# Battery_Manager.net
KiCad netlist of a schematic drawn in Altium Designer
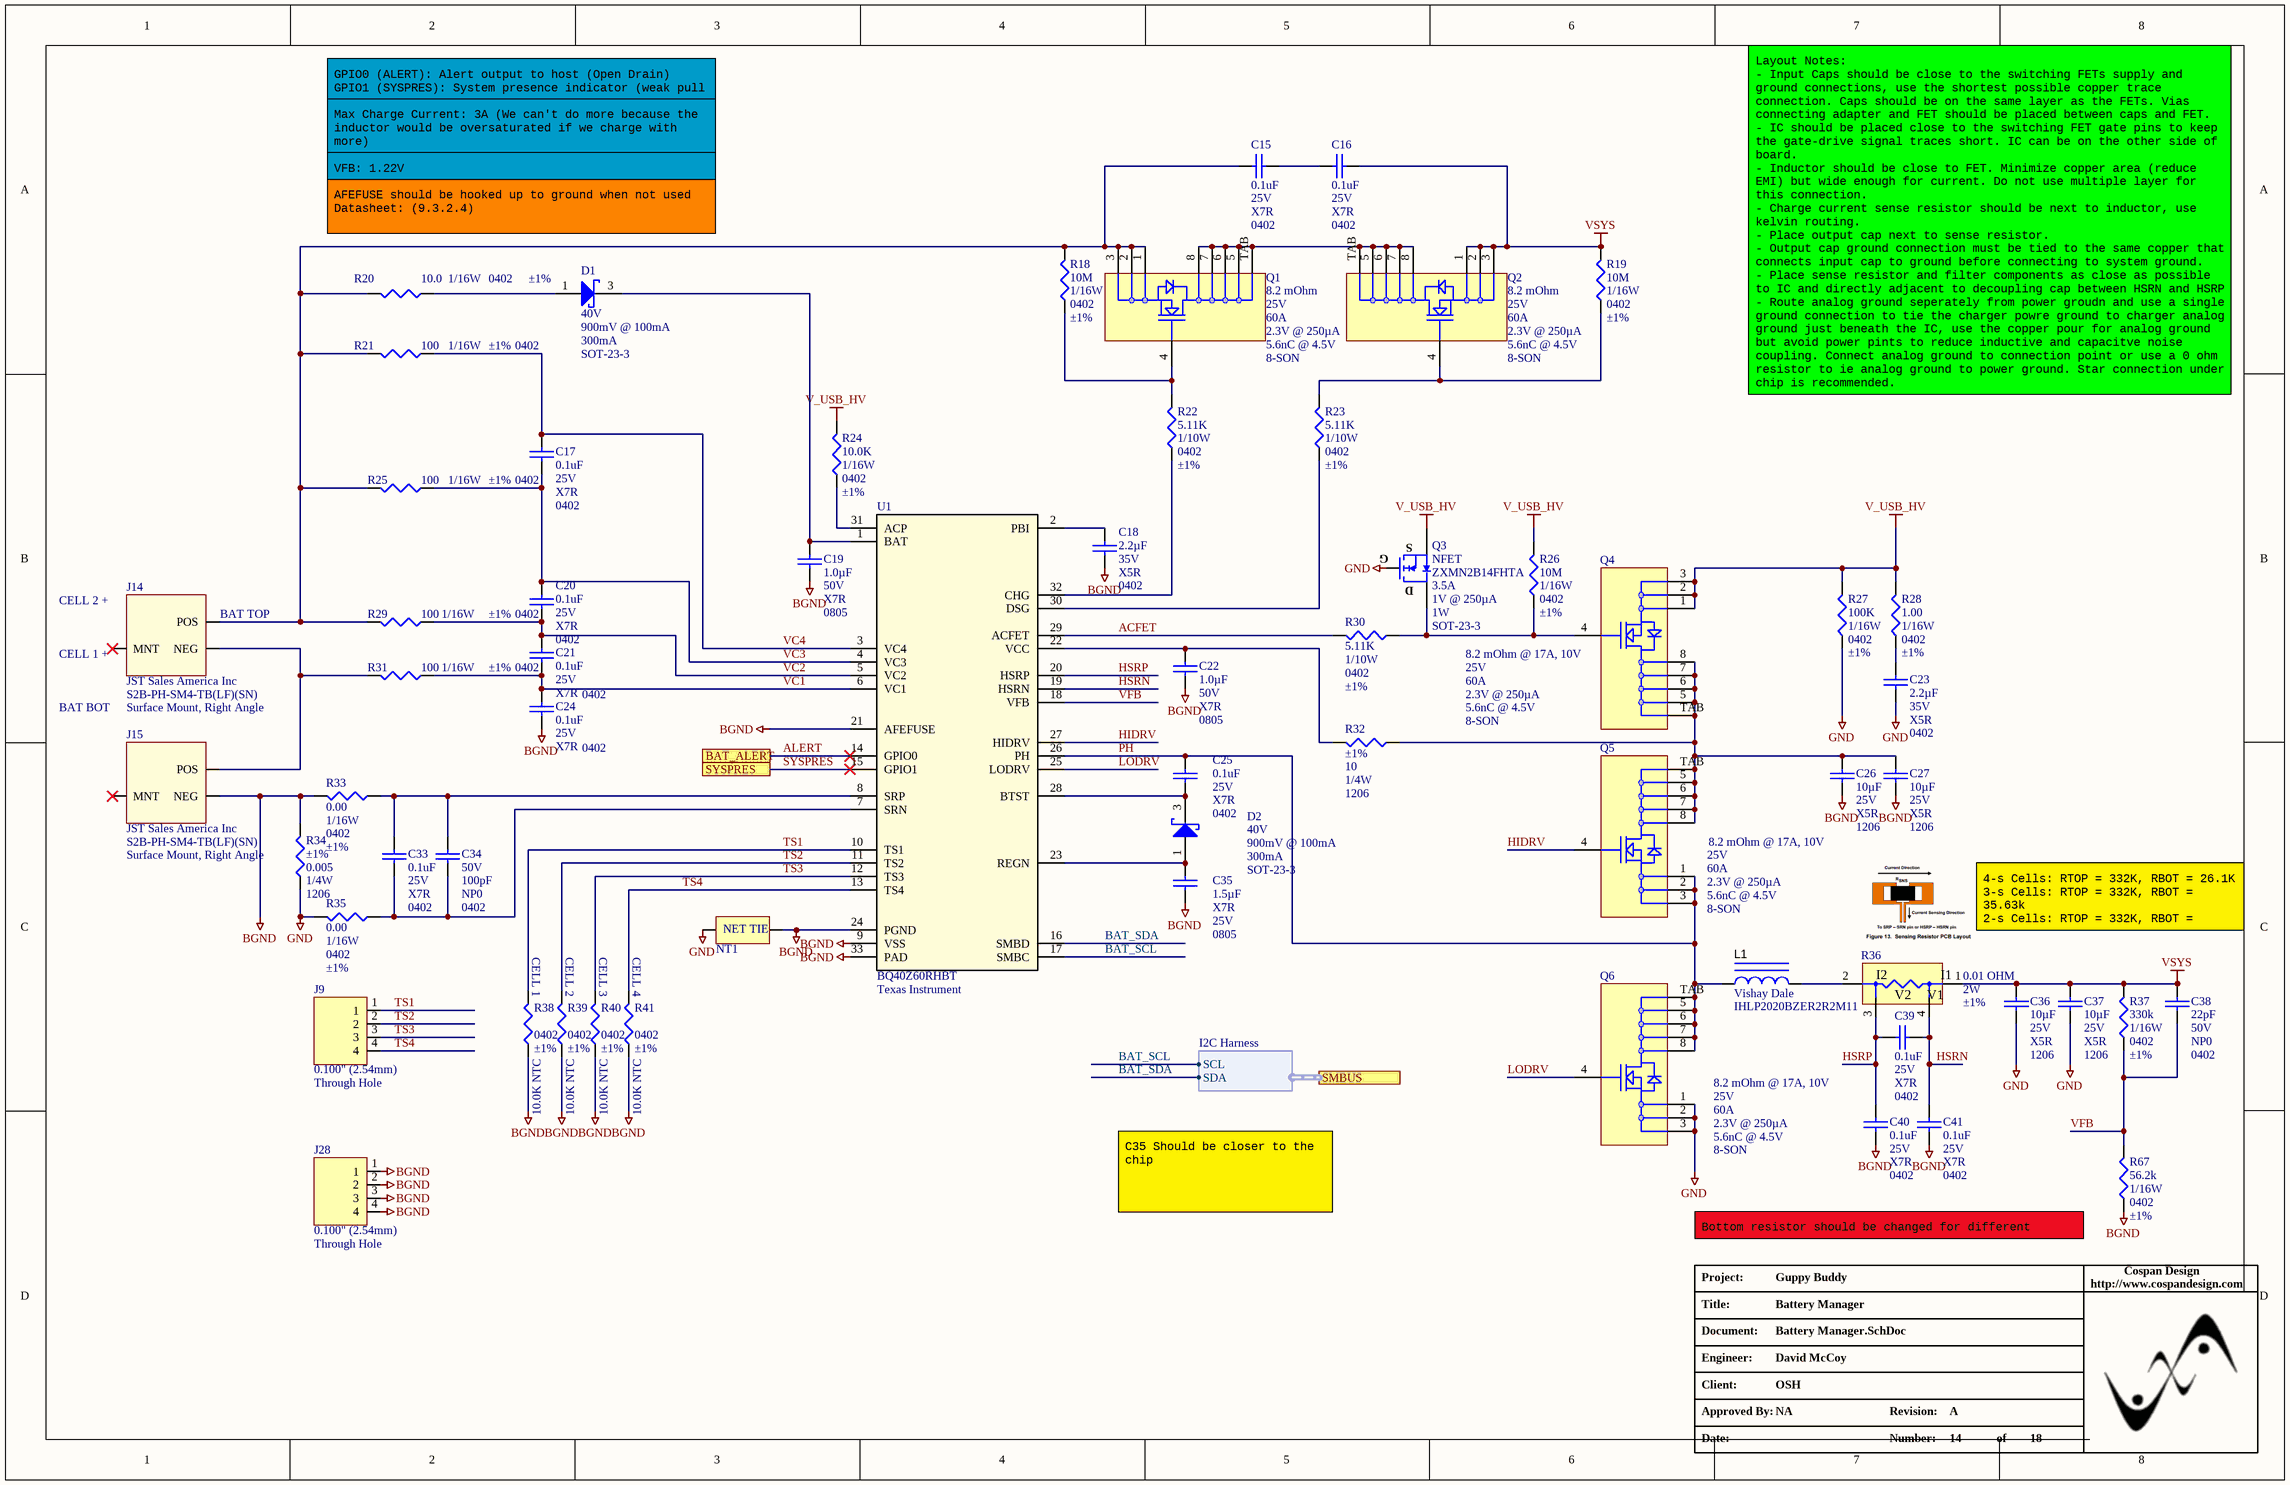
[diagram p0: Battery Manager.SchDoc]

(export (version "E")
  (design (tool "Eeschema 10.0.6"))
  (components
    (comp (ref "C15")
      (value "C_0402_0.1UF_25V")
      (footprint "C_0402")
      (description "CAP CER 0.1UF 25V X6S 0402")
      (fields
        (field (name "TOLERANCE") "10%")
        (field (name "CAPACITANCE") "0.1uF")
        (field (name "VOLTAGE - RATED") "25V")
        (field (name "TEMPERATURE COEFFICIENT") "X7R")
        (field (name "PACKAGE / CASE") "0402")
      )
      (libsource (lib "Cospan Design") (part "C_0402_0.1UF_25V"))
    )
    (comp (ref "C16")
      (value "C_0402_0.1UF_25V")
      (footprint "C_0402")
      (description "CAP CER 0.1UF 25V X6S 0402")
      (fields
        (field (name "TOLERANCE") "10%")
        (field (name "CAPACITANCE") "0.1uF")
        (field (name "VOLTAGE - RATED") "25V")
        (field (name "TEMPERATURE COEFFICIENT") "X7R")
        (field (name "PACKAGE / CASE") "0402")
      )
      (libsource (lib "Cospan Design") (part "C_0402_0.1UF_25V"))
    )
    (comp (ref "C17")
      (value "C_0402_0.1UF_25V")
      (footprint "C_0402")
      (description "CAP CER 0.1UF 25V X6S 0402")
      (fields
        (field (name "TOLERANCE") "10%")
        (field (name "CAPACITANCE") "0.1uF")
        (field (name "VOLTAGE - RATED") "25V")
        (field (name "TEMPERATURE COEFFICIENT") "X7R")
        (field (name "PACKAGE / CASE") "0402")
      )
      (libsource (lib "Cospan Design") (part "C_0402_0.1UF_25V"))
    )
    (comp (ref "C18")
      (value "C_0402_2.2uF_35V")
      (footprint "C_ERA-0402")
      (description "CAP CER 2.2UF 35V 20% X5R 0402")
      (fields
        (field (name "MANUFACTURER") "TDK Corporation")
        (field (name "MANUFACTURER PART NUMBER") "C1005X5R1V225K050BC")
        (field (name "CAPACITANCE") "2.2µF")
        (field (name "VOLTAGE - RATED") "35V")
        (field (name "TEMPERATURE COEFFICIENT") "X5R")
        (field (name "PACKAGE / CASE") "0402")
      )
      (libsource (lib "Main LibraryX") (part "C_0402_2.2uF_35V"))
    )
    (comp (ref "C19")
      (value "1.0uF")
      (footprint "C_ERA-0805")
      (description "CAP CER 1UF 50V X7R 0805")
      (fields
        (field (name "TOLERANCE") "10%")
        (field (name "CAPACITANCE") "1.0µF")
        (field (name "VOLTAGE - RATED") "50V")
        (field (name "TEMPERATURE COEFFICIENT") "X7R")
        (field (name "PACKAGE / CASE") "0805")
        (field (name "VOLTAGE") "50V")
      )
      (libsource (lib "Main LibraryX") (part "C_0805_1.0uF_50V"))
    )
    (comp (ref "C20")
      (value "C_0402_0.1UF_25V")
      (footprint "C_0402")
      (description "CAP CER 0.1UF 25V X6S 0402")
      (fields
        (field (name "TOLERANCE") "10%")
        (field (name "CAPACITANCE") "0.1uF")
        (field (name "VOLTAGE - RATED") "25V")
        (field (name "TEMPERATURE COEFFICIENT") "X7R")
        (field (name "PACKAGE / CASE") "0402")
      )
      (libsource (lib "Cospan Design") (part "C_0402_0.1UF_25V"))
    )
    (comp (ref "C21")
      (value "C_0402_0.1UF_25V")
      (footprint "C_0402")
      (description "CAP CER 0.1UF 25V X6S 0402")
      (fields
        (field (name "TOLERANCE") "10%")
        (field (name "CAPACITANCE") "0.1uF")
        (field (name "VOLTAGE - RATED") "25V")
        (field (name "TEMPERATURE COEFFICIENT") "X7R")
        (field (name "PACKAGE / CASE") "0402")
      )
      (libsource (lib "Cospan Design") (part "C_0402_0.1UF_25V"))
    )
    (comp (ref "C22")
      (value "1.0uF")
      (footprint "C_ERA-0805")
      (description "CAP CER 1UF 50V X7R 0805")
      (fields
        (field (name "TOLERANCE") "10%")
        (field (name "CAPACITANCE") "1.0µF")
        (field (name "VOLTAGE - RATED") "50V")
        (field (name "TEMPERATURE COEFFICIENT") "X7R")
        (field (name "PACKAGE / CASE") "0805")
        (field (name "VOLTAGE") "50V")
      )
      (libsource (lib "Main LibraryX") (part "C_0805_1.0uF_50V"))
    )
    (comp (ref "C23")
      (value "C_0402_2.2uF_35V")
      (footprint "C_ERA-0402")
      (description "CAP CER 2.2UF 35V 20% X5R 0402")
      (fields
        (field (name "MANUFACTURER") "TDK Corporation")
        (field (name "MANUFACTURER PART NUMBER") "C1005X5R1V225K050BC")
        (field (name "CAPACITANCE") "2.2µF")
        (field (name "VOLTAGE - RATED") "35V")
        (field (name "TEMPERATURE COEFFICIENT") "X5R")
        (field (name "PACKAGE / CASE") "0402")
      )
      (libsource (lib "Main LibraryX") (part "C_0402_2.2uF_35V"))
    )
    (comp (ref "C24")
      (value "C_0402_0.1UF_25V")
      (footprint "C_0402")
      (description "CAP CER 0.1UF 25V X6S 0402")
      (fields
        (field (name "TOLERANCE") "10%")
        (field (name "CAPACITANCE") "0.1uF")
        (field (name "VOLTAGE - RATED") "25V")
        (field (name "TEMPERATURE COEFFICIENT") "X7R")
        (field (name "PACKAGE / CASE") "0402")
      )
      (libsource (lib "Cospan Design") (part "C_0402_0.1UF_25V"))
    )
    (comp (ref "C25")
      (value "C_0402_0.1UF_25V")
      (footprint "C_0402")
      (description "CAP CER 0.1UF 25V X6S 0402")
      (fields
        (field (name "TOLERANCE") "10%")
        (field (name "CAPACITANCE") "0.1uF")
        (field (name "VOLTAGE - RATED") "25V")
        (field (name "TEMPERATURE COEFFICIENT") "X7R")
        (field (name "PACKAGE / CASE") "0402")
      )
      (libsource (lib "Cospan Design") (part "C_0402_0.1UF_25V"))
    )
    (comp (ref "C26")
      (value "10µF")
      (footprint "CAP-1206")
      (description "CAP CER 10UF 25V X5R 1206")
      (fields
        (field (name "TOLERANCE") "10%")
        (field (name "CAPACITANCE") "10µF")
        (field (name "VOLTAGE - RATED") "25V")
        (field (name "TEMPERATURE COEFFICIENT") "X5R")
        (field (name "PACKAGE / CASE") "1206")
        (field (name "VOLTAGE") "25V")
      )
      (libsource (lib "Main LibraryX") (part "C_1206_10UF_25V"))
    )
    (comp (ref "C27")
      (value "10µF")
      (footprint "CAP-1206")
      (description "CAP CER 10UF 25V X5R 1206")
      (fields
        (field (name "TOLERANCE") "10%")
        (field (name "CAPACITANCE") "10µF")
        (field (name "VOLTAGE - RATED") "25V")
        (field (name "TEMPERATURE COEFFICIENT") "X5R")
        (field (name "PACKAGE / CASE") "1206")
        (field (name "VOLTAGE") "25V")
      )
      (libsource (lib "Main LibraryX") (part "C_1206_10UF_25V"))
    )
    (comp (ref "C33")
      (value "C_0402_0.1UF_25V")
      (footprint "C_0402")
      (description "CAP CER 0.1UF 25V X6S 0402")
      (fields
        (field (name "TOLERANCE") "10%")
        (field (name "CAPACITANCE") "0.1uF")
        (field (name "VOLTAGE - RATED") "25V")
        (field (name "TEMPERATURE COEFFICIENT") "X7R")
        (field (name "PACKAGE / CASE") "0402")
      )
      (libsource (lib "Cospan Design") (part "C_0402_0.1UF_25V"))
    )
    (comp (ref "C34")
      (value "100pF")
      (footprint "C_0402")
      (description "CAP CER 100PF 50V 5% C0G 0402")
      (fields
        (field (name "MANUFACTURER") "Murata Electronics North America")
        (field (name "MANUFACTURER PART NUMBER") "GRM1555C1H101JA01D")
        (field (name "VOLTAGE - RATED") "50V")
        (field (name "CAPACITANCE") "100pF")
        (field (name "TEMPERATURE COEFFICIENT") "NP0")
        (field (name "PACKAGE / CASE") "0402")
      )
      (libsource (lib "Main LibraryX") (part "C_0402_100PF"))
    )
    (comp (ref "C35")
      (value "C_0805_1.5uF_25V")
      (footprint "C_ERA-0805")
      (description "1.5µF ±10% 25V Ceramic Capacitor X7R 0805 (2012 Metric)")
      (fields
        (field (name "MANUFACTURER") "Murata Electronics North America")
        (field (name "MANUFACTURER PART NUMBER") "GRM21BR71E155KA88L")
        (field (name "CAPACITANCE") "1.5µF")
        (field (name "VOLTAGE - RATED") "X7R")
        (field (name "TEMPERATURE COEFFICIENT") "25V")
        (field (name "PACKAGE / CASE") "0805")
      )
      (libsource (lib "Cospan Design") (part "C_0805_1.5uF_25V"))
    )
    (comp (ref "C36")
      (value "10µF")
      (footprint "CAP-1206")
      (description "CAP CER 10UF 25V X5R 1206")
      (fields
        (field (name "TOLERANCE") "10%")
        (field (name "CAPACITANCE") "10µF")
        (field (name "VOLTAGE - RATED") "25V")
        (field (name "TEMPERATURE COEFFICIENT") "X5R")
        (field (name "PACKAGE / CASE") "1206")
        (field (name "VOLTAGE") "25V")
      )
      (libsource (lib "Main LibraryX") (part "C_1206_10UF_25V"))
    )
    (comp (ref "C37")
      (value "10µF")
      (footprint "CAP-1206")
      (description "CAP CER 10UF 25V X5R 1206")
      (fields
        (field (name "TOLERANCE") "10%")
        (field (name "CAPACITANCE") "10µF")
        (field (name "VOLTAGE - RATED") "25V")
        (field (name "TEMPERATURE COEFFICIENT") "X5R")
        (field (name "PACKAGE / CASE") "1206")
        (field (name "VOLTAGE") "25V")
      )
      (libsource (lib "Main LibraryX") (part "C_1206_10UF_25V"))
    )
    (comp (ref "C38")
      (value "22pF")
      (footprint "C_ERA-0402")
      (description "CAP CER 22PF 50V NP0 0402")
      (fields
        (field (name "MANUFACTURER") "Murata Electronics North America")
        (field (name "MANUFACTURER PART NUMBER") "GRM1555C1H220FA01D")
        (field (name "CAPACITANCE") "22pF")
        (field (name "VOLTAGE - RATED") "50V")
        (field (name "TEMPERATURE COEFFICIENT") "NP0")
        (field (name "PACKAGE / CASE") "0402")
      )
      (libsource (lib "Main LibraryX") (part "C_0402_22PF_50V"))
    )
    (comp (ref "C39")
      (value "C_0402_0.1UF_25V")
      (footprint "C_0402")
      (description "CAP CER 0.1UF 25V X6S 0402")
      (fields
        (field (name "TOLERANCE") "10%")
        (field (name "CAPACITANCE") "0.1uF")
        (field (name "VOLTAGE - RATED") "25V")
        (field (name "TEMPERATURE COEFFICIENT") "X7R")
        (field (name "PACKAGE / CASE") "0402")
      )
      (libsource (lib "Cospan Design") (part "C_0402_0.1UF_25V"))
    )
    (comp (ref "C40")
      (value "C_0402_0.1UF_25V")
      (footprint "C_0402")
      (description "CAP CER 0.1UF 25V X6S 0402")
      (fields
        (field (name "TOLERANCE") "10%")
        (field (name "CAPACITANCE") "0.1uF")
        (field (name "VOLTAGE - RATED") "25V")
        (field (name "TEMPERATURE COEFFICIENT") "X7R")
        (field (name "PACKAGE / CASE") "0402")
      )
      (libsource (lib "Cospan Design") (part "C_0402_0.1UF_25V"))
    )
    (comp (ref "C41")
      (value "C_0402_0.1UF_25V")
      (footprint "C_0402")
      (description "CAP CER 0.1UF 25V X6S 0402")
      (fields
        (field (name "TOLERANCE") "10%")
        (field (name "CAPACITANCE") "0.1uF")
        (field (name "VOLTAGE - RATED") "25V")
        (field (name "TEMPERATURE COEFFICIENT") "X7R")
        (field (name "PACKAGE / CASE") "0402")
      )
      (libsource (lib "Cospan Design") (part "C_0402_0.1UF_25V"))
    )
    (comp (ref "D1")
      (value "BAT54")
      (footprint "SOT23")
      (description "DIODE SCHOTTKY 40V 300MA SOT-23")
      (fields
        (field (name "VOLTAGE - DC REVERSE (VR) (MAX)") "40V")
        (field (name "VOLTAGE - FORWARD (VF) (MAX) @ IF") "900mV @ 100mA")
        (field (name "CURRENT - AVERAGE RECTIFIED (IO)") "300mA")
        (field (name "PACKAGE / CASE") "SOT-23-3")
      )
      (libsource (lib "Main Library") (part "D_SCHOTT_BAT54WFILM"))
    )
    (comp (ref "D2")
      (value "BAT54")
      (footprint "SOT23")
      (description "DIODE SCHOTTKY 40V 300MA SOT-23")
      (fields
        (field (name "VOLTAGE - DC REVERSE (VR) (MAX)") "40V")
        (field (name "VOLTAGE - FORWARD (VF) (MAX) @ IF") "900mV @ 100mA")
        (field (name "CURRENT - AVERAGE RECTIFIED (IO)") "300mA")
        (field (name "PACKAGE / CASE") "SOT-23-3")
      )
      (libsource (lib "Main Library") (part "D_SCHOTT_BAT54WFILM"))
    )
    (comp (ref "J9")
      (value "J_HDR1X4_THRHOLE_VERT")
      (footprint "HDR_1X4")
      (description "CONN HEADER .100\" 4POS TIN PCB")
      (fields
        (field (name "MANUFACTURER") "Samtec")
        (field (name "MANUFACTURER PART NUMBER") "TSW-104-07-T-S")
        (field (name "PITCH") "0.100\" (2.54mm)")
        (field (name "MOUNTING TYPE") "Through Hole")
      )
      (libsource (lib "Main Library") (part "J_HDR1X4_THRHOLE_VERT"))
    )
    (comp (ref "J14")
      (value "J_LIPO_BAT_CONNECTOR")
      (footprint "HDR_1X2_LIPO_BATTERY")
      (description "CONN HEADER PH SIDE 2POS 2MM SMD")
      (fields
        (field (name "MANUFACTURER") "JST Sales America Inc")
        (field (name "MANUFACTURER PART NUMBER") "S2B-PH-SM4-TB(LF)(SN)")
        (field (name "MOUNTING TYPE") "Surface Mount, Right Angle")
      )
      (libsource (lib "Main Library") (part "J_LIPO_BAT_CONNECTOR"))
    )
    (comp (ref "J15")
      (value "J_LIPO_BAT_CONNECTOR")
      (footprint "HDR_1X2_LIPO_BATTERY")
      (description "CONN HEADER PH SIDE 2POS 2MM SMD")
      (fields
        (field (name "MANUFACTURER") "JST Sales America Inc")
        (field (name "MANUFACTURER PART NUMBER") "S2B-PH-SM4-TB(LF)(SN)")
        (field (name "MOUNTING TYPE") "Surface Mount, Right Angle")
      )
      (libsource (lib "Main Library") (part "J_LIPO_BAT_CONNECTOR"))
    )
    (comp (ref "J28")
      (value "J_HDR1X4_THRHOLE_VERT")
      (footprint "HDR_1X4")
      (description "CONN HEADER .100\" 4POS TIN PCB")
      (fields
        (field (name "MANUFACTURER") "Samtec")
        (field (name "MANUFACTURER PART NUMBER") "TSW-104-07-T-S")
        (field (name "PITCH") "0.100\" (2.54mm)")
        (field (name "MOUNTING TYPE") "Through Hole")
      )
      (libsource (lib "Main Library") (part "J_HDR1X4_THRHOLE_VERT"))
    )
    (comp (ref "L1")
      (value "L_IHLP2020BZER2R2M11")
      (footprint "IHLP-2020BZ")
      (description "2.2µH Shielded Molded Inductor 5A 37.7 mOhm Max")
      (fields
        (field (name "TOLERANCE") "±20%")
        (field (name "MANUFACTURER") "Vishay Dale")
        (field (name "MANUFACTURER PART NUMBER") "IHLP2020BZER2R2M11")
      )
      (libsource (lib "Cospan Design") (part "L_IHLP2020BZER2R2M11"))
    )
    (comp (ref "NT1")
      (value "NET_TIE")
      (footprint "NET_TIE")
      (libsource (lib "Cospan Design") (part "NET_TIE"))
    )
    (comp (ref "Q1")
      (value "N-Channel Nex_FET")
      (footprint "Q_TDSON-8 NexFET")
      (description "MOSFET N-CH 25V 60A 8-SON")
      (fields
        (field (name "MANUFACTURER") "Texas Instruments")
        (field (name "MANUFACTURER PART NUMBER") "CSD16409Q3")
        (field (name "RDS ON (MAX) @ ID, VGS") "8.2 mOhm")
        (field (name "DRAIN TO SOURCE VOLTAGE (VDSS)") "25V")
        (field (name "CURRENT - CONTINUOUS DRAIN (ID) @ 25° C") "60A")
        (field (name "VGS(TH) (MAX) @ ID") "2.3V @ 250µA")
        (field (name "GATE CHARGE (QG) @ VGS") "5.6nC @ 4.5V")
        (field (name "PACKAGE / CASE") "8-SON")
      )
      (libsource (lib "Main Library") (part "Q_N-CH_8SON_60A_9.5mOHM"))
    )
    (comp (ref "Q2")
      (value "N-Channel Nex_FET")
      (footprint "Q_TDSON-8 NexFET")
      (description "MOSFET N-CH 25V 60A 8-SON")
      (fields
        (field (name "MANUFACTURER") "Texas Instruments")
        (field (name "MANUFACTURER PART NUMBER") "CSD16409Q3")
        (field (name "RDS ON (MAX) @ ID, VGS") "8.2 mOhm")
        (field (name "DRAIN TO SOURCE VOLTAGE (VDSS)") "25V")
        (field (name "CURRENT - CONTINUOUS DRAIN (ID) @ 25° C") "60A")
        (field (name "VGS(TH) (MAX) @ ID") "2.3V @ 250µA")
        (field (name "GATE CHARGE (QG) @ VGS") "5.6nC @ 4.5V")
        (field (name "PACKAGE / CASE") "8-SON")
      )
      (libsource (lib "Main Library") (part "Q_N-CH_8SON_60A_9.5mOHM"))
    )
    (comp (ref "Q3")
      (value "NFET")
      (footprint "SOT-23A")
      (description "MOSFET N-CH 20V 3.5A SOT23-3")
      (fields
        (field (name "MANUFACTURER") "Diodes/Zetex")
        (field (name "MANUFACTURER PART NUMBER") "ZXMN2B14FHTA")
        (field (name "CURRENT - CONTINUOUS DRAIN (ID) @ 25° C") "3.5A")
        (field (name "VGS(TH) (MAX) @ ID") "1V @ 250µA")
        (field (name "POWER - MAX") "1W")
        (field (name "PACKAGE / CASE") "SOT-23-3")
      )
      (libsource (lib "Main LibraryX") (part "Q_NFET_3.50A_SOT23"))
    )
    (comp (ref "Q4")
      (value "N-Channel Nex_FET")
      (footprint "Q_TDSON-8 NexFET")
      (description "MOSFET N-CH 25V 60A 8-SON")
      (fields
        (field (name "MANUFACTURER") "Texas Instruments")
        (field (name "MANUFACTURER PART NUMBER") "CSD16409Q3")
        (field (name "RDS ON (MAX) @ ID, VGS") "8.2 mOhm @ 17A, 10V")
        (field (name "DRAIN TO SOURCE VOLTAGE (VDSS)") "25V")
        (field (name "CURRENT - CONTINUOUS DRAIN (ID) @ 25° C") "60A")
        (field (name "VGS(TH) (MAX) @ ID") "2.3V @ 250µA")
        (field (name "GATE CHARGE (QG) @ VGS") "5.6nC @ 4.5V")
        (field (name "PACKAGE / CASE") "8-SON")
      )
      (libsource (lib "Main Library") (part "Q_N-CH_8SON_60A_9.5mOHM"))
    )
    (comp (ref "Q5")
      (value "N-Channel Nex_FET")
      (footprint "Q_TDSON-8 NexFET")
      (description "MOSFET N-CH 25V 60A 8-SON")
      (fields
        (field (name "MANUFACTURER") "Texas Instruments")
        (field (name "MANUFACTURER PART NUMBER") "CSD16409Q3")
        (field (name "RDS ON (MAX) @ ID, VGS") "8.2 mOhm @ 17A, 10V")
        (field (name "DRAIN TO SOURCE VOLTAGE (VDSS)") "25V")
        (field (name "CURRENT - CONTINUOUS DRAIN (ID) @ 25° C") "60A")
        (field (name "VGS(TH) (MAX) @ ID") "2.3V @ 250µA")
        (field (name "GATE CHARGE (QG) @ VGS") "5.6nC @ 4.5V")
        (field (name "PACKAGE / CASE") "8-SON")
      )
      (libsource (lib "Main Library") (part "Q_N-CH_8SON_60A_9.5mOHM"))
    )
    (comp (ref "Q6")
      (value "N-Channel Nex_FET")
      (footprint "Q_TDSON-8 NexFET")
      (description "MOSFET N-CH 25V 60A 8-SON")
      (fields
        (field (name "MANUFACTURER") "Texas Instruments")
        (field (name "MANUFACTURER PART NUMBER") "CSD16409Q3")
        (field (name "RDS ON (MAX) @ ID, VGS") "8.2 mOhm @ 17A, 10V")
        (field (name "DRAIN TO SOURCE VOLTAGE (VDSS)") "25V")
        (field (name "CURRENT - CONTINUOUS DRAIN (ID) @ 25° C") "60A")
        (field (name "VGS(TH) (MAX) @ ID") "2.3V @ 250µA")
        (field (name "GATE CHARGE (QG) @ VGS") "5.6nC @ 4.5V")
        (field (name "PACKAGE / CASE") "8-SON")
      )
      (libsource (lib "Main Library") (part "Q_N-CH_8SON_60A_9.5mOHM"))
    )
    (comp (ref "R18")
      (value "R_0402_10M")
      (footprint "R_0402")
      (description "RES SMD 10M OHM 1% 1/16W 0402")
      (fields
        (field (name "MANUFACTURER") "Yageo")
        (field (name "MANUFACTURER PART NUMBER") "RC0402FR-0710ML")
        (field (name "RESISTANCE IN OHMS") "10M")
        (field (name "POWER (WATTS)") "1/16W")
        (field (name "CASE") "0402")
        (field (name "TOLERANCE") "±1%")
      )
      (libsource (lib "Cospan Design") (part "R_0402_10M"))
    )
    (comp (ref "R19")
      (value "R_0402_10M")
      (footprint "R_0402")
      (description "RES SMD 10M OHM 1% 1/16W 0402")
      (fields
        (field (name "MANUFACTURER") "Yageo")
        (field (name "MANUFACTURER PART NUMBER") "RC0402FR-0710ML")
        (field (name "RESISTANCE IN OHMS") "10M")
        (field (name "POWER (WATTS)") "1/16W")
        (field (name "CASE") "0402")
        (field (name "TOLERANCE") "±1%")
      )
      (libsource (lib "Cospan Design") (part "R_0402_10M"))
    )
    (comp (ref "R20")
      (value "R_0402_10.0")
      (footprint "R_0402")
      (description "RES 10.0 OHM 1/16W 1% 0402 SMD")
      (fields
        (field (name "MANUFACTURER") "Yageo")
        (field (name "MANUFACTURER PART NUMBER") "RC0402FR-0710RL")
        (field (name "RESISTANCE IN OHMS") "10.0")
        (field (name "POWER (WATTS)") "1/16W")
        (field (name "CASE") "0402")
        (field (name "TOLERANCE") "±1%")
      )
      (libsource (lib "Main LibraryX") (part "R_0402_10.0"))
    )
    (comp (ref "R21")
      (value "R_0402_100.0")
      (footprint "R_0402")
      (description "RES 100 OHM 1/16W 1% 0402 SMD")
      (fields
        (field (name "MANUFACTURER") "Yageo")
        (field (name "MANUFACTURER PART NUMBER") "RC0402FR-07100RL")
        (field (name "CASE") "0402")
        (field (name "RESISTANCE IN OHMS") "100")
        (field (name "POWER (WATTS)") "1/16W")
        (field (name "TOLERANCE") "±1%")
      )
      (libsource (lib "Main LibraryX") (part "R_0402_100.0"))
    )
    (comp (ref "R22")
      (value "5.11k Ohms")
      (footprint "R_0402")
      (description "RES 5.11K OHM 1/10W 1% 0402 SMD")
      (fields
        (field (name "MANUFACTURER") "Panasonic - ECG")
        (field (name "MANUFACTURER PART NUMBER") "ERJ-2RKF5111X")
        (field (name "RESISTANCE IN OHMS") "5.11K")
        (field (name "POWER (WATTS)") "1/10W")
        (field (name "CASE") "0402")
        (field (name "TOLERANCE") "±1%")
      )
      (libsource (lib "Main Library") (part "R_0402_5.11K"))
    )
    (comp (ref "R23")
      (value "5.11k Ohms")
      (footprint "R_0402")
      (description "RES 5.11K OHM 1/10W 1% 0402 SMD")
      (fields
        (field (name "MANUFACTURER") "Panasonic - ECG")
        (field (name "MANUFACTURER PART NUMBER") "ERJ-2RKF5111X")
        (field (name "RESISTANCE IN OHMS") "5.11K")
        (field (name "POWER (WATTS)") "1/10W")
        (field (name "CASE") "0402")
        (field (name "TOLERANCE") "±1%")
      )
      (libsource (lib "Main Library") (part "R_0402_5.11K"))
    )
    (comp (ref "R24")
      (value "R_0402_10.0K")
      (footprint "R_0402")
      (description "RES 10.0K OHM 1/16W 1% 0402 SMD")
      (fields
        (field (name "MANUFACTURER") "Stackpole Electronics Inc")
        (field (name "MANUFACTURER PART NUMBER") "RMCF0402FT10K0")
        (field (name "RESISTANCE IN OHMS") "10.0K")
        (field (name "POWER (WATTS)") "1/16W")
        (field (name "CASE") "0402")
        (field (name "TOLERANCE") "±1%")
      )
      (libsource (lib "Main Library") (part "R_0402_10.0K"))
    )
    (comp (ref "R25")
      (value "R_0402_100.0")
      (footprint "R_0402")
      (description "RES 100 OHM 1/16W 1% 0402 SMD")
      (fields
        (field (name "MANUFACTURER") "Yageo")
        (field (name "MANUFACTURER PART NUMBER") "RC0402FR-07100RL")
        (field (name "CASE") "0402")
        (field (name "RESISTANCE IN OHMS") "100")
        (field (name "POWER (WATTS)") "1/16W")
        (field (name "TOLERANCE") "±1%")
      )
      (libsource (lib "Main LibraryX") (part "R_0402_100.0"))
    )
    (comp (ref "R26")
      (value "R_0402_10M")
      (footprint "R_0402")
      (description "RES SMD 10M OHM 1% 1/16W 0402")
      (fields
        (field (name "MANUFACTURER") "Yageo")
        (field (name "MANUFACTURER PART NUMBER") "RC0402FR-0710ML")
        (field (name "RESISTANCE IN OHMS") "10M")
        (field (name "POWER (WATTS)") "1/16W")
        (field (name "CASE") "0402")
        (field (name "TOLERANCE") "±1%")
      )
      (libsource (lib "Cospan Design") (part "R_0402_10M"))
    )
    (comp (ref "R27")
      (value "R_0402_100.0K")
      (footprint "R_0402")
      (description "RES 100K OHM 1/16W 1% 0402 SMD")
      (fields
        (field (name "MANUFACTURER") "Stackpole Electronics Inc")
        (field (name "MANUFACTURER PART NUMBER") "RMCF0402FT100K")
        (field (name "RESISTANCE IN OHMS") "100K")
        (field (name "POWER (WATTS)") "1/16W")
        (field (name "CASE") "0402")
        (field (name "TOLERANCE") "±1%")
      )
      (libsource (lib "Main Library") (part "R_0402_100.0K"))
    )
    (comp (ref "R28")
      (value "1.0 Ohms")
      (footprint "R_0402")
      (description "RES 1.00 OHM 1/16W 1% 0402 SMD")
      (fields
        (field (name "MANUFACTURER") "Yageo")
        (field (name "MANUFACTURER PART NUMBER") "RC0402FR-071RL")
        (field (name "RESISTANCE IN OHMS") "1.00")
        (field (name "POWER (WATTS)") "1/16W")
        (field (name "CASE") "0402")
        (field (name "TOLERANCE") "±1%")
      )
      (libsource (lib "Main Library") (part "R_0402_1.00"))
    )
    (comp (ref "R29")
      (value "R_0402_100.0")
      (footprint "R_0402")
      (description "RES 100 OHM 1/16W 1% 0402 SMD")
      (fields
        (field (name "MANUFACTURER") "Yageo")
        (field (name "MANUFACTURER PART NUMBER") "RC0402FR-07100RL")
        (field (name "CASE") "0402")
        (field (name "RESISTANCE IN OHMS") "100")
        (field (name "POWER (WATTS)") "1/16W")
        (field (name "TOLERANCE") "±1%")
      )
      (libsource (lib "Main LibraryX") (part "R_0402_100.0"))
    )
    (comp (ref "R30")
      (value "5.11k Ohms")
      (footprint "R_0402")
      (description "RES 5.11K OHM 1/10W 1% 0402 SMD")
      (fields
        (field (name "MANUFACTURER") "Panasonic - ECG")
        (field (name "MANUFACTURER PART NUMBER") "ERJ-2RKF5111X")
        (field (name "RESISTANCE IN OHMS") "5.11K")
        (field (name "POWER (WATTS)") "1/10W")
        (field (name "CASE") "0402")
        (field (name "TOLERANCE") "±1%")
      )
      (libsource (lib "Main Library") (part "R_0402_5.11K"))
    )
    (comp (ref "R31")
      (value "R_0402_100.0")
      (footprint "R_0402")
      (description "RES 100 OHM 1/16W 1% 0402 SMD")
      (fields
        (field (name "MANUFACTURER") "Yageo")
        (field (name "MANUFACTURER PART NUMBER") "RC0402FR-07100RL")
        (field (name "CASE") "0402")
        (field (name "RESISTANCE IN OHMS") "100")
        (field (name "POWER (WATTS)") "1/16W")
        (field (name "TOLERANCE") "±1%")
      )
      (libsource (lib "Main LibraryX") (part "R_0402_100.0"))
    )
    (comp (ref "R32")
      (value "R_1206_10")
      (footprint "R_1206")
      (description "RES SMD 10 OHM 1% 1/4W 1206")
      (fields
        (field (name "MANUFACTURER") "Yageo")
        (field (name "MANUFACTURER PART NUMBER") "RC1206FR-0710RL")
        (field (name "TOLERANCE") "±1%")
        (field (name "RESISTANCE IN OHMS") "10")
        (field (name "POWER (WATTS)") "1/4W")
        (field (name "CASE") "1206")
      )
      (libsource (lib "Cospan Design") (part "R_1206_10"))
    )
    (comp (ref "R33")
      (value "0.0 Ohms")
      (footprint "R_0402")
      (description "RES 0.00 OHM 1/16W 1% 0402 SMD")
      (fields
        (field (name "MANUFACTURER") "Yageo")
        (field (name "MANUFACTURER PART NUMBER") "RC0402JR-070RL")
        (field (name "RESISTANCE IN OHMS") "0.00")
        (field (name "POWER (WATTS)") "1/16W")
        (field (name "CASE") "0402")
        (field (name "TOLERANCE") "±1%")
      )
      (libsource (lib "Cospan Design") (part "R_0402_0.00"))
    )
    (comp (ref "R34")
      (value "R_1206_0.005")
      (footprint "R_1206")
      (description "RES SMD 0.005 OHM 1% 1W 1206")
      (fields
        (field (name "MANUFACTURER") "Stackpole Electronics Inc.")
        (field (name "MANUFACTURER PART NUMBER") "CSRF1206FT5L00")
        (field (name "TOLERANCE") "±1%")
        (field (name "RESISTANCE IN OHMS") "0.005")
        (field (name "POWER (WATTS)") "1/4W")
        (field (name "CASE") "1206")
      )
      (libsource (lib "Cospan Design") (part "R_1206_0.005"))
    )
    (comp (ref "R35")
      (value "0.0 Ohms")
      (footprint "R_0402")
      (description "RES 0.00 OHM 1/16W 1% 0402 SMD")
      (fields
        (field (name "MANUFACTURER") "Yageo")
        (field (name "MANUFACTURER PART NUMBER") "RC0402JR-070RL")
        (field (name "RESISTANCE IN OHMS") "0.00")
        (field (name "POWER (WATTS)") "1/16W")
        (field (name "CASE") "0402")
        (field (name "TOLERANCE") "±1%")
      )
      (libsource (lib "Cospan Design") (part "R_0402_0.00"))
    )
    (comp (ref "R36")
      (value "0.01 OHM")
      (footprint "R_LVK25_0.003")
      (description "RES SMD 0.01 OHM 1% 2W 1224")
      (fields
        (field (name "MANUFACTURER") "Ohmite")
        (field (name "MANUFACTURER PART NUMBER") "LVK25R010FER")
        (field (name "POWER (WATTS)") "2W")
        (field (name "TOLERANCE") "±1%")
      )
      (libsource (lib "Main Library") (part "R_0.010SENSE_LK20"))
    )
    (comp (ref "R37")
      (value "R_0402_330K")
      (footprint "R_0402")
      (description "RES SMD 330K OHM 1% 1/16W 0402")
      (fields
        (field (name "MANUFACTURER") "Yageo")
        (field (name "MANUFACTURER PART NUMBER") "RC0402FR-07330KL")
        (field (name "RESISTANCE IN OHMS") "330k")
        (field (name "POWER (WATTS)") "1/16W")
        (field (name "CASE") "0402")
        (field (name "TOLERANCE") "±1%")
      )
      (libsource (lib "Cospan Design") (part "R_0402_330K"))
    )
    (comp (ref "R38")
      (value "R_0402_NTC_10.0K")
      (footprint "R_0402")
      (description "NTC Thermistor 10k 0402 (1005 Metric)")
      (fields
        (field (name "MANUFACTURER") "Murata Electronics North America")
        (field (name "MANUFACTURER PART NUMBER") "NCP15XH103F03RC")
        (field (name "RESISTANCE IN OHMS") "10.0K NTC")
        (field (name "CASE") "0402")
        (field (name "TOLERANCE") "±1%")
      )
      (libsource (lib "Cospan Design") (part "R_0402_NTC_10.0K"))
    )
    (comp (ref "R39")
      (value "R_0402_NTC_10.0K")
      (footprint "R_0402")
      (description "NTC Thermistor 10k 0402 (1005 Metric)")
      (fields
        (field (name "MANUFACTURER") "Murata Electronics North America")
        (field (name "MANUFACTURER PART NUMBER") "NCP15XH103F03RC")
        (field (name "RESISTANCE IN OHMS") "10.0K NTC")
        (field (name "CASE") "0402")
        (field (name "TOLERANCE") "±1%")
      )
      (libsource (lib "Cospan Design") (part "R_0402_NTC_10.0K"))
    )
    (comp (ref "R40")
      (value "R_0402_NTC_10.0K")
      (footprint "R_0402")
      (description "NTC Thermistor 10k 0402 (1005 Metric)")
      (fields
        (field (name "MANUFACTURER") "Murata Electronics North America")
        (field (name "MANUFACTURER PART NUMBER") "NCP15XH103F03RC")
        (field (name "RESISTANCE IN OHMS") "10.0K NTC")
        (field (name "CASE") "0402")
        (field (name "TOLERANCE") "±1%")
      )
      (libsource (lib "Cospan Design") (part "R_0402_NTC_10.0K"))
    )
    (comp (ref "R41")
      (value "R_0402_NTC_10.0K")
      (footprint "R_0402")
      (description "NTC Thermistor 10k 0402 (1005 Metric)")
      (fields
        (field (name "MANUFACTURER") "Murata Electronics North America")
        (field (name "MANUFACTURER PART NUMBER") "NCP15XH103F03RC")
        (field (name "RESISTANCE IN OHMS") "10.0K NTC")
        (field (name "CASE") "0402")
        (field (name "TOLERANCE") "±1%")
      )
      (libsource (lib "Cospan Design") (part "R_0402_NTC_10.0K"))
    )
    (comp (ref "R67")
      (value "56.2k")
      (footprint "R_0402")
      (description "RES 56.2K OHM 1/16W 1% 0402 SMD")
      (fields
        (field (name "MANUFACTURER") "Vishay Dale")
        (field (name "MANUFACTURER PART NUMBER") "CRCW040256K2FKED")
        (field (name "RESISTANCE IN OHMS") "56.2k")
        (field (name "POWER (WATTS)") "1/16W")
        (field (name "CASE") "0402")
        (field (name "TOLERANCE") "±1%")
      )
      (libsource (lib "Main Library") (part "R_0402_56.2k"))
    )
    (comp (ref "U1")
      (value "U_BQ40Z60RHBR")
      (footprint "RHB0032E")
      (description "IC BATTERY MANAGER 32VQFN")
      (fields
        (field (name "MANUFACTURER PART NUMBER") "BQ40Z60RHBT")
        (field (name "MANUFACTURER") "Texas Instrument")
      )
      (libsource (lib "Cospan Design") (part "U_BQ40Z60RHBR"))
    )
  )
  (nets
    (net (code "3") (name "/ACFET") (class "Default")
      (node (ref "R30") (pin "1") (pinfunction "1_1") (pintype "passive"))
      (node (ref "U1") (pin "29") (pinfunction "ACFET_29") (pintype "passive"))
    )
    (net (code "4") (name "/ALERT") (class "Default")
      (node (ref "U1") (pin "14") (pinfunction "GPIO0_14") (pintype "passive+no_connect"))
    )
    (net (code "5") (name "/BAT_SCL") (class "Default")
      (node (ref "U1") (pin "17") (pinfunction "SMBC_17") (pintype "passive"))
    )
    (net (code "6") (name "/BAT_SDA") (class "Default")
      (node (ref "U1") (pin "16") (pinfunction "SMBD_16") (pintype "passive"))
    )
    (net (code "7") (name "/HIDRV") (class "Default")
      (node (ref "Q5") (pin "4") (pinfunction "G1_4") (pintype "passive"))
      (node (ref "U1") (pin "27") (pinfunction "HIDRV_27") (pintype "passive"))
    )
    (net (code "8") (name "/HSRN") (class "Default")
      (node (ref "C39") (pin "1") (pinfunction "1_1") (pintype "passive"))
      (node (ref "C41") (pin "1") (pinfunction "1_1") (pintype "passive"))
      (node (ref "R36") (pin "4") (pinfunction "V1_4") (pintype "passive"))
      (node (ref "U1") (pin "19") (pinfunction "HSRN_19") (pintype "passive"))
    )
    (net (code "9") (name "/HSRP") (class "Default")
      (node (ref "C39") (pin "2") (pinfunction "2_2") (pintype "passive"))
      (node (ref "C40") (pin "1") (pinfunction "1_1") (pintype "passive"))
      (node (ref "R36") (pin "3") (pinfunction "V2_3") (pintype "passive"))
      (node (ref "U1") (pin "20") (pinfunction "HSRP_20") (pintype "passive"))
    )
    (net (code "10") (name "/LODRV") (class "Default")
      (node (ref "Q6") (pin "4") (pinfunction "G1_4") (pintype "passive"))
      (node (ref "U1") (pin "25") (pinfunction "LODRV_25") (pintype "passive"))
    )
    (net (code "11") (name "/PH") (class "Default")
      (node (ref "C25") (pin "1") (pinfunction "1_1") (pintype "passive"))
      (node (ref "L1") (pin "2") (pinfunction "2_2") (pintype "passive"))
      (node (ref "Q5") (pin "1") (pinfunction "S1_1") (pintype "passive"))
      (node (ref "Q5") (pin "2") (pintype "passive"))
      (node (ref "Q5") (pin "3") (pintype "passive"))
      (node (ref "Q6") (pin "5") (pintype "passive"))
      (node (ref "Q6") (pin "6") (pintype "passive"))
      (node (ref "Q6") (pin "7") (pinfunction "D2a_7") (pintype "passive"))
      (node (ref "Q6") (pin "8") (pinfunction "D2b_8") (pintype "passive"))
      (node (ref "Q6") (pin "TAB") (pintype "passive"))
      (node (ref "U1") (pin "26") (pinfunction "PH_26") (pintype "passive"))
    )
    (net (code "12") (name "/SYSPRES") (class "Default")
      (node (ref "U1") (pin "15") (pinfunction "GPIO1_15") (pintype "passive+no_connect"))
    )
    (net (code "13") (name "/TS1") (class "Default")
      (node (ref "J9") (pin "1") (pinfunction "1_1") (pintype "passive"))
      (node (ref "R38") (pin "1") (pinfunction "1_1") (pintype "passive"))
      (node (ref "U1") (pin "10") (pinfunction "TS1_10") (pintype "passive"))
    )
    (net (code "14") (name "/TS2") (class "Default")
      (node (ref "J9") (pin "2") (pinfunction "2_2") (pintype "passive"))
      (node (ref "R39") (pin "1") (pinfunction "1_1") (pintype "passive"))
      (node (ref "U1") (pin "11") (pinfunction "TS2_11") (pintype "passive"))
    )
    (net (code "15") (name "/TS3") (class "Default")
      (node (ref "J9") (pin "3") (pinfunction "3_3") (pintype "passive"))
      (node (ref "R40") (pin "1") (pinfunction "1_1") (pintype "passive"))
      (node (ref "U1") (pin "12") (pinfunction "TS3_12") (pintype "passive"))
    )
    (net (code "16") (name "/TS4") (class "Default")
      (node (ref "J9") (pin "4") (pinfunction "4_4") (pintype "passive"))
      (node (ref "R41") (pin "1") (pinfunction "1_1") (pintype "passive"))
      (node (ref "U1") (pin "13") (pinfunction "TS4_13") (pintype "passive"))
    )
    (net (code "17") (name "/VC1") (class "Default")
      (node (ref "C21") (pin "1") (pinfunction "1_1") (pintype "passive"))
      (node (ref "C24") (pin "2") (pinfunction "2_2") (pintype "passive"))
      (node (ref "R31") (pin "2") (pinfunction "2_2") (pintype "passive"))
      (node (ref "U1") (pin "6") (pinfunction "VC1_6") (pintype "passive"))
    )
    (net (code "18") (name "/VC2") (class "Default")
      (node (ref "C20") (pin "1") (pinfunction "1_1") (pintype "passive"))
      (node (ref "C21") (pin "2") (pinfunction "2_2") (pintype "passive"))
      (node (ref "R29") (pin "2") (pinfunction "2_2") (pintype "passive"))
      (node (ref "U1") (pin "5") (pinfunction "VC2_5") (pintype "passive"))
    )
    (net (code "19") (name "/VC3") (class "Default")
      (node (ref "C17") (pin "1") (pinfunction "1_1") (pintype "passive"))
      (node (ref "C20") (pin "2") (pinfunction "2_2") (pintype "passive"))
      (node (ref "R25") (pin "2") (pinfunction "2_2") (pintype "passive"))
      (node (ref "U1") (pin "4") (pinfunction "VC3_4") (pintype "passive"))
    )
    (net (code "20") (name "/VC4") (class "Default")
      (node (ref "C17") (pin "2") (pinfunction "2_2") (pintype "passive"))
      (node (ref "R21") (pin "2") (pinfunction "2_2") (pintype "passive"))
      (node (ref "U1") (pin "3") (pinfunction "VC4_3") (pintype "passive"))
    )
    (net (code "21") (name "/VFB") (class "Default")
      (node (ref "C38") (pin "1") (pinfunction "1_1") (pintype "passive"))
      (node (ref "R37") (pin "2") (pinfunction "2_2") (pintype "passive"))
      (node (ref "R67") (pin "1") (pinfunction "1_1") (pintype "passive"))
      (node (ref "U1") (pin "18") (pinfunction "VFB_18") (pintype "passive"))
    )
    (net (code "23") (name "BGND") (class "Default")
      (node (ref "C18") (pin "1") (pinfunction "1_1") (pintype "passive"))
      (node (ref "C19") (pin "1") (pinfunction "1_1") (pintype "passive"))
      (node (ref "C22") (pin "1") (pinfunction "1_1") (pintype "passive"))
      (node (ref "C24") (pin "1") (pinfunction "1_1") (pintype "passive"))
      (node (ref "C26") (pin "1") (pinfunction "1_1") (pintype "passive"))
      (node (ref "C27") (pin "1") (pinfunction "1_1") (pintype "passive"))
      (node (ref "C35") (pin "1") (pinfunction "1_1") (pintype "passive"))
      (node (ref "C40") (pin "2") (pinfunction "2_2") (pintype "passive"))
      (node (ref "C41") (pin "2") (pinfunction "2_2") (pintype "passive"))
      (node (ref "J15") (pin "2") (pinfunction "NEG_2") (pintype "passive"))
      (node (ref "J28") (pin "1") (pinfunction "1_1") (pintype "passive"))
      (node (ref "J28") (pin "2") (pinfunction "2_2") (pintype "passive"))
      (node (ref "J28") (pin "3") (pinfunction "3_3") (pintype "passive"))
      (node (ref "J28") (pin "4") (pinfunction "4_4") (pintype "passive"))
      (node (ref "NT1") (pin "2") (pinfunction "2_2") (pintype "passive"))
      (node (ref "R33") (pin "1") (pinfunction "1_1") (pintype "passive"))
      (node (ref "R34") (pin "1") (pinfunction "1_1") (pintype "passive"))
      (node (ref "R38") (pin "2") (pinfunction "2_2") (pintype "passive"))
      (node (ref "R39") (pin "2") (pinfunction "2_2") (pintype "passive"))
      (node (ref "R40") (pin "2") (pinfunction "2_2") (pintype "passive"))
      (node (ref "R41") (pin "2") (pinfunction "2_2") (pintype "passive"))
      (node (ref "R67") (pin "2") (pinfunction "2_2") (pintype "passive"))
      (node (ref "U1") (pin "21") (pinfunction "AFEFUSE_21") (pintype "passive"))
      (node (ref "U1") (pin "24") (pinfunction "PGND_24") (pintype "passive"))
      (node (ref "U1") (pin "33") (pinfunction "PAD_33") (pintype "passive"))
      (node (ref "U1") (pin "9") (pinfunction "VSS_9") (pintype "passive"))
    )
    (net (code "24") (name "GND") (class "Default")
      (node (ref "C23") (pin "1") (pinfunction "1_1") (pintype "passive"))
      (node (ref "C36") (pin "2") (pinfunction "2_2") (pintype "passive"))
      (node (ref "C37") (pin "2") (pinfunction "2_2") (pintype "passive"))
      (node (ref "NT1") (pin "1") (pinfunction "1_1") (pintype "passive"))
      (node (ref "Q3") (pin "1") (pinfunction "G_1") (pintype "passive"))
      (node (ref "Q6") (pin "1") (pinfunction "S1_1") (pintype "passive"))
      (node (ref "Q6") (pin "2") (pintype "passive"))
      (node (ref "Q6") (pin "3") (pintype "passive"))
      (node (ref "R27") (pin "2") (pinfunction "2_2") (pintype "passive"))
      (node (ref "R34") (pin "2") (pinfunction "2_2") (pintype "passive"))
      (node (ref "R35") (pin "1") (pinfunction "1_1") (pintype "passive"))
    )
    (net (code "25") (name "Net-(C15-Pad1)") (class "Default")
      (node (ref "C15") (pin "1") (pinfunction "1_1") (pintype "passive"))
      (node (ref "C16") (pin "2") (pinfunction "2_2") (pintype "passive"))
    )
    (net (code "26") (name "Net-(C23-Pad2)") (class "Default")
      (node (ref "C23") (pin "2") (pinfunction "2_2") (pintype "passive"))
      (node (ref "R28") (pin "2") (pinfunction "2_2") (pintype "passive"))
    )
    (net (code "27") (name "Net-(D1-A)") (class "Default")
      (node (ref "D1") (pin "1") (pinfunction "A_1") (pintype "passive"))
      (node (ref "R20") (pin "2") (pinfunction "2_2") (pintype "passive"))
    )
    (net (code "28") (name "Net-(D1-K)") (class "Default")
      (node (ref "C19") (pin "2") (pinfunction "2_2") (pintype "passive"))
      (node (ref "D1") (pin "3") (pinfunction "K_3") (pintype "passive"))
      (node (ref "U1") (pin "1") (pinfunction "BAT_1") (pintype "passive"))
    )
    (net (code "29") (name "Net-(D2-A)") (class "Default")
      (node (ref "C35") (pin "2") (pinfunction "2_2") (pintype "passive"))
      (node (ref "D2") (pin "1") (pinfunction "A_1") (pintype "passive"))
      (node (ref "U1") (pin "23") (pinfunction "REGN_23") (pintype "passive"))
    )
    (net (code "30") (name "Net-(D2-K)") (class "Default")
      (node (ref "C25") (pin "2") (pinfunction "2_2") (pintype "passive"))
      (node (ref "D2") (pin "3") (pinfunction "K_3") (pintype "passive"))
      (node (ref "U1") (pin "28") (pinfunction "BTST_28") (pintype "passive"))
    )
    (net (code "31") (name "Net-(J14-NEG)") (class "Default")
      (node (ref "J14") (pin "2") (pinfunction "NEG_2") (pintype "passive"))
      (node (ref "J15") (pin "1") (pinfunction "POS_1") (pintype "passive"))
      (node (ref "R31") (pin "1") (pinfunction "1_1") (pintype "passive"))
    )
    (net (code "32") (name "Net-(J14-POS)") (class "Default")
      (node (ref "C15") (pin "2") (pinfunction "2_2") (pintype "passive"))
      (node (ref "J14") (pin "1") (pinfunction "POS_1") (pintype "passive"))
      (node (ref "Q1") (pin "1") (pinfunction "S1_1") (pintype "passive"))
      (node (ref "Q1") (pin "2") (pintype "passive"))
      (node (ref "Q1") (pin "3") (pintype "passive"))
      (node (ref "R18") (pin "1") (pinfunction "1_1") (pintype "passive"))
      (node (ref "R20") (pin "1") (pinfunction "1_1") (pintype "passive"))
      (node (ref "R21") (pin "1") (pinfunction "1_1") (pintype "passive"))
      (node (ref "R25") (pin "1") (pinfunction "1_1") (pintype "passive"))
      (node (ref "R29") (pin "1") (pinfunction "1_1") (pintype "passive"))
    )
    (net (code "33") (name "Net-(Q1-D2a)") (class "Default")
      (node (ref "Q1") (pin "5") (pintype "passive"))
      (node (ref "Q1") (pin "6") (pintype "passive"))
      (node (ref "Q1") (pin "7") (pinfunction "D2a_7") (pintype "passive"))
      (node (ref "Q1") (pin "8") (pinfunction "D2b_8") (pintype "passive"))
      (node (ref "Q1") (pin "TAB") (pintype "passive"))
      (node (ref "Q2") (pin "5") (pintype "passive"))
      (node (ref "Q2") (pin "6") (pintype "passive"))
      (node (ref "Q2") (pin "7") (pinfunction "D2a_7") (pintype "passive"))
      (node (ref "Q2") (pin "8") (pinfunction "D2b_8") (pintype "passive"))
      (node (ref "Q2") (pin "TAB") (pintype "passive"))
    )
    (net (code "34") (name "Net-(Q1-G1)") (class "Default")
      (node (ref "Q1") (pin "4") (pinfunction "G1_4") (pintype "passive"))
      (node (ref "R18") (pin "2") (pinfunction "2_2") (pintype "passive"))
      (node (ref "R22") (pin "1") (pinfunction "1_1") (pintype "passive"))
    )
    (net (code "35") (name "Net-(Q2-G1)") (class "Default")
      (node (ref "Q2") (pin "4") (pinfunction "G1_4") (pintype "passive"))
      (node (ref "R19") (pin "2") (pinfunction "2_2") (pintype "passive"))
      (node (ref "R23") (pin "1") (pinfunction "1_1") (pintype "passive"))
    )
    (net (code "36") (name "Net-(Q3-D)") (class "Default")
      (node (ref "Q3") (pin "3") (pinfunction "D_3") (pintype "passive"))
      (node (ref "Q4") (pin "4") (pinfunction "G1_4") (pintype "passive"))
      (node (ref "R26") (pin "2") (pinfunction "2_2") (pintype "passive"))
      (node (ref "R30") (pin "2") (pinfunction "2_2") (pintype "passive"))
    )
    (net (code "37") (name "Net-(Q4-D2a)") (class "Default")
      (node (ref "C26") (pin "2") (pinfunction "2_2") (pintype "passive"))
      (node (ref "C27") (pin "2") (pinfunction "2_2") (pintype "passive"))
      (node (ref "Q4") (pin "5") (pintype "passive"))
      (node (ref "Q4") (pin "6") (pintype "passive"))
      (node (ref "Q4") (pin "7") (pinfunction "D2a_7") (pintype "passive"))
      (node (ref "Q4") (pin "8") (pinfunction "D2b_8") (pintype "passive"))
      (node (ref "Q4") (pin "TAB") (pintype "passive"))
      (node (ref "Q5") (pin "5") (pintype "passive"))
      (node (ref "Q5") (pin "6") (pintype "passive"))
      (node (ref "Q5") (pin "7") (pinfunction "D2a_7") (pintype "passive"))
      (node (ref "Q5") (pin "8") (pinfunction "D2b_8") (pintype "passive"))
      (node (ref "Q5") (pin "TAB") (pintype "passive"))
      (node (ref "R32") (pin "2") (pinfunction "2_2") (pintype "passive"))
    )
    (net (code "38") (name "Net-(R36-I2)") (class "Default")
      (node (ref "L1") (pin "1") (pinfunction "1_1") (pintype "passive"))
      (node (ref "R36") (pin "2") (pinfunction "I2_2") (pintype "passive"))
    )
    (net (code "39") (name "Net-(U1-ACP)") (class "Default")
      (node (ref "R24") (pin "2") (pinfunction "2_2") (pintype "passive"))
      (node (ref "U1") (pin "31") (pinfunction "ACP_31") (pintype "passive"))
    )
    (net (code "40") (name "Net-(U1-CHG)") (class "Default")
      (node (ref "R22") (pin "2") (pinfunction "2_2") (pintype "passive"))
      (node (ref "U1") (pin "32") (pinfunction "CHG_32") (pintype "passive"))
    )
    (net (code "41") (name "Net-(U1-DSG)") (class "Default")
      (node (ref "R23") (pin "2") (pinfunction "2_2") (pintype "passive"))
      (node (ref "U1") (pin "30") (pinfunction "DSG_30") (pintype "passive"))
    )
    (net (code "42") (name "Net-(U1-PBI)") (class "Default")
      (node (ref "C18") (pin "2") (pinfunction "2_2") (pintype "passive"))
      (node (ref "U1") (pin "2") (pinfunction "PBI_2") (pintype "passive"))
    )
    (net (code "43") (name "Net-(U1-SRN)") (class "Default")
      (node (ref "C33") (pin "2") (pinfunction "2_2") (pintype "passive"))
      (node (ref "C34") (pin "1") (pinfunction "1_1") (pintype "passive"))
      (node (ref "R35") (pin "2") (pinfunction "2_2") (pintype "passive"))
      (node (ref "U1") (pin "7") (pinfunction "SRN_7") (pintype "passive"))
    )
    (net (code "44") (name "Net-(U1-SRP)") (class "Default")
      (node (ref "C33") (pin "1") (pinfunction "1_1") (pintype "passive"))
      (node (ref "C34") (pin "2") (pinfunction "2_2") (pintype "passive"))
      (node (ref "R33") (pin "2") (pinfunction "2_2") (pintype "passive"))
      (node (ref "U1") (pin "8") (pinfunction "SRP_8") (pintype "passive"))
    )
    (net (code "45") (name "Net-(U1-VCC)") (class "Default")
      (node (ref "C22") (pin "2") (pinfunction "2_2") (pintype "passive"))
      (node (ref "R32") (pin "1") (pinfunction "1_1") (pintype "passive"))
      (node (ref "U1") (pin "22") (pinfunction "VCC_22") (pintype "passive"))
    )
    (net (code "46") (name "VSYS") (class "Default")
      (node (ref "C16") (pin "1") (pinfunction "1_1") (pintype "passive"))
      (node (ref "C36") (pin "1") (pinfunction "1_1") (pintype "passive"))
      (node (ref "C37") (pin "1") (pinfunction "1_1") (pintype "passive"))
      (node (ref "C38") (pin "2") (pinfunction "2_2") (pintype "passive"))
      (node (ref "Q2") (pin "1") (pinfunction "S1_1") (pintype "passive"))
      (node (ref "Q2") (pin "2") (pintype "passive"))
      (node (ref "Q2") (pin "3") (pintype "passive"))
      (node (ref "R19") (pin "1") (pinfunction "1_1") (pintype "passive"))
      (node (ref "R36") (pin "1") (pinfunction "I1_1") (pintype "passive"))
      (node (ref "R37") (pin "1") (pinfunction "1_1") (pintype "passive"))
    )
    (net (code "47") (name "V_USB_HV") (class "Default")
      (node (ref "Q3") (pin "2") (pinfunction "S_2") (pintype "passive"))
      (node (ref "Q4") (pin "1") (pinfunction "S1_1") (pintype "passive"))
      (node (ref "Q4") (pin "2") (pintype "passive"))
      (node (ref "Q4") (pin "3") (pintype "passive"))
      (node (ref "R24") (pin "1") (pinfunction "1_1") (pintype "passive"))
      (node (ref "R26") (pin "1") (pinfunction "1_1") (pintype "passive"))
      (node (ref "R27") (pin "1") (pinfunction "1_1") (pintype "passive"))
      (node (ref "R28") (pin "1") (pinfunction "1_1") (pintype "passive"))
    )
    (net (code "48") (name "unconnected-(J14-PadMNT)") (class "Default")
      (node (ref "J14") (pin "MNT") (pinfunction "MNT_MNT") (pintype "passive+no_connect"))
    )
    (net (code "49") (name "unconnected-(J15-PadMNT)") (class "Default")
      (node (ref "J15") (pin "MNT") (pinfunction "MNT_MNT") (pintype "passive+no_connect"))
    )
  )
)
